# ATOM_-_3x_Attenuverter_Rev6.net
KiCad netlist of a schematic drawn in EAGLE
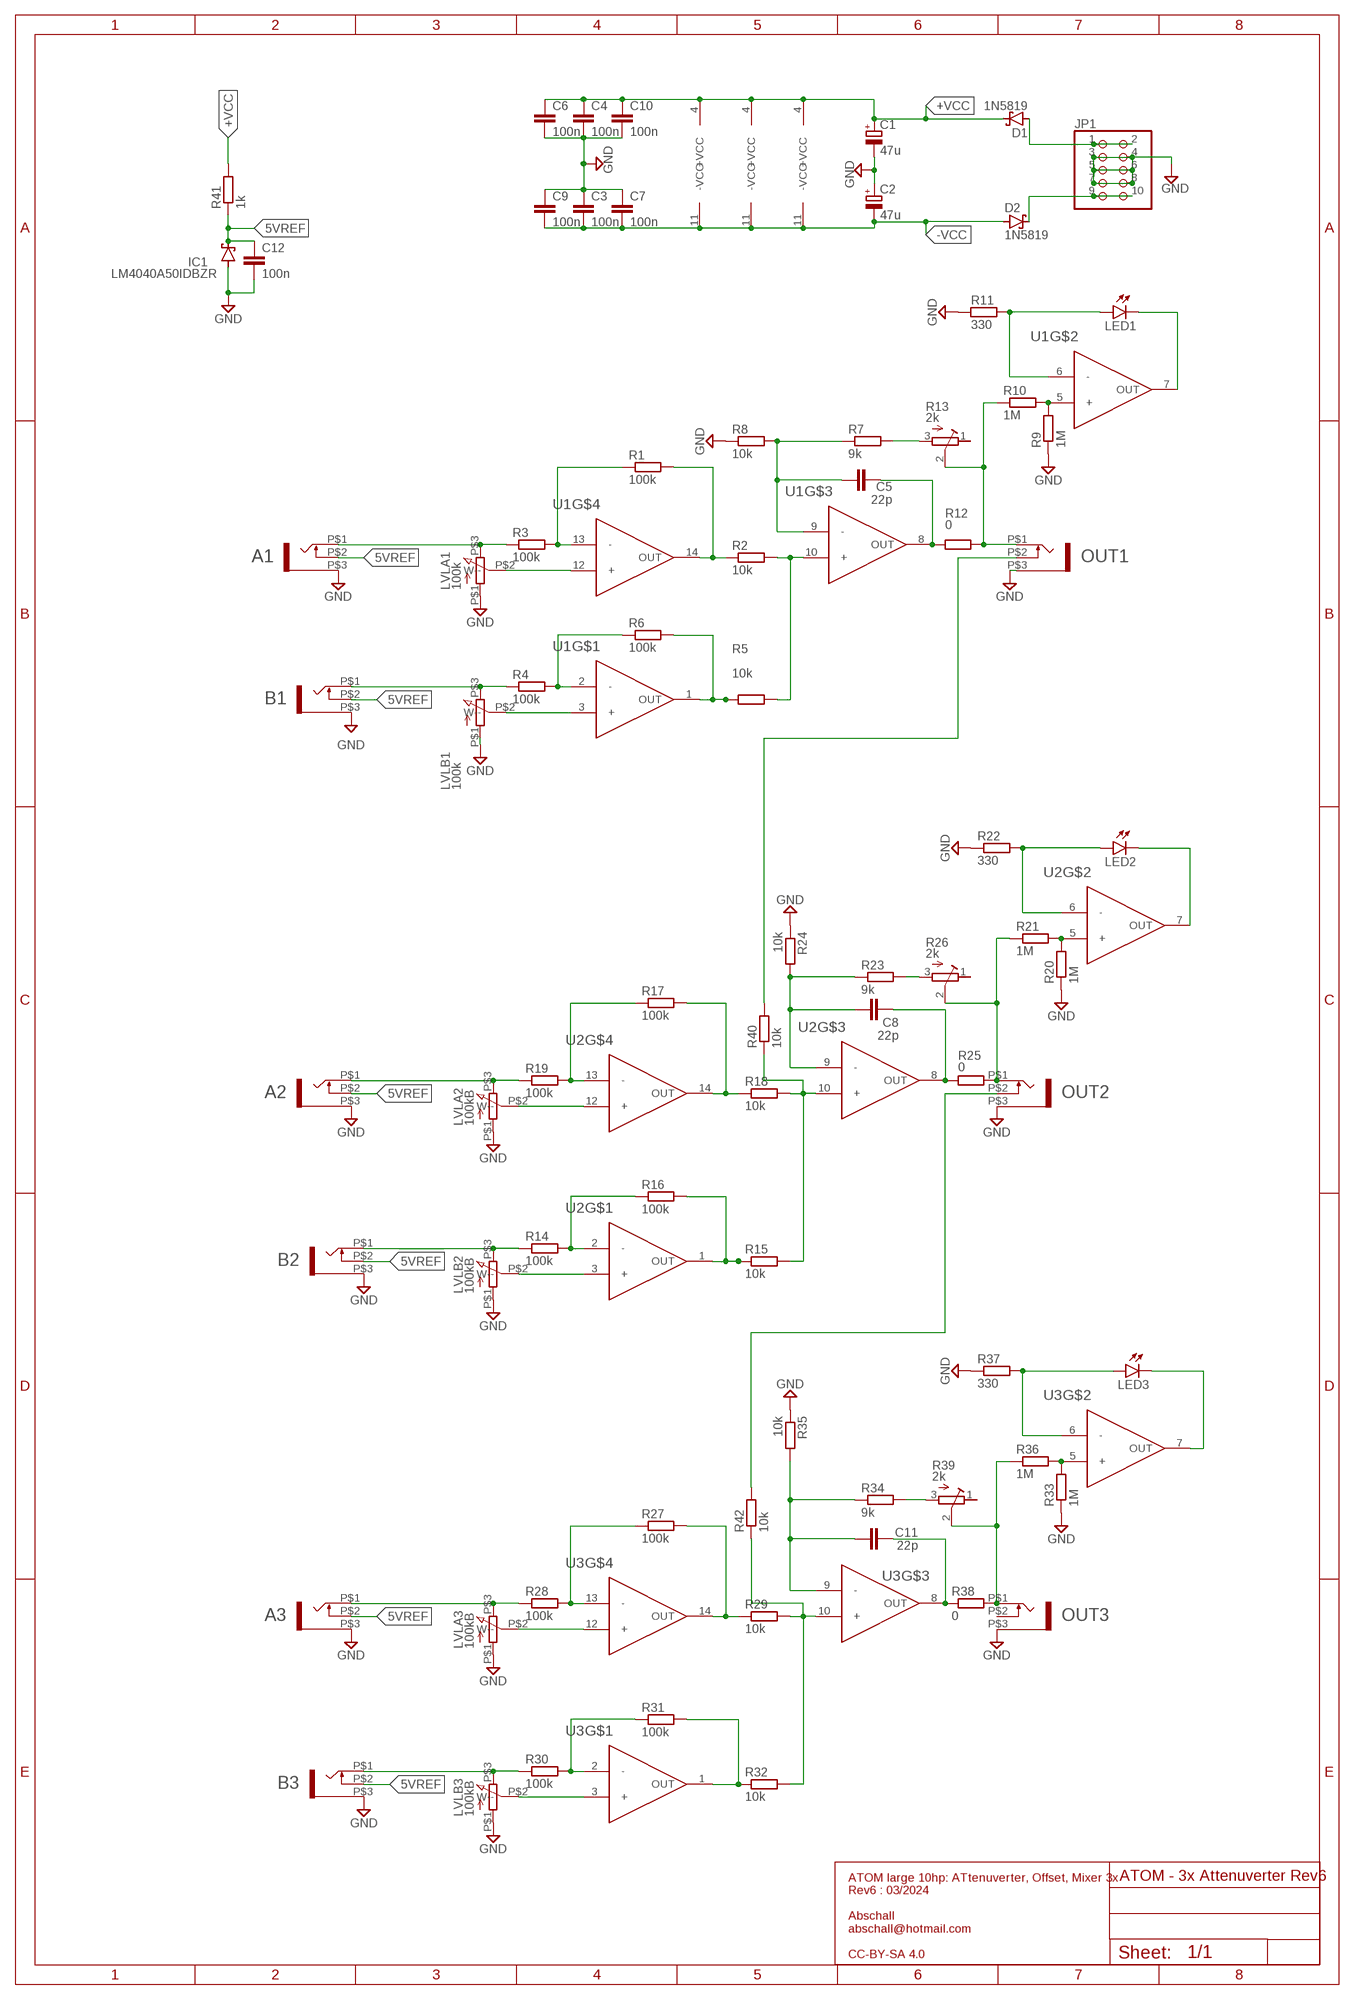
[diagram p0: schematic, sheet 1]

(export (version "E")
  (design (tool "Eeschema 10.0.6"))
  (components
    (comp (ref "A1")
      (value "WQP-PJ301M-12_JACK")
      (footprint "eagle-import:WQP-PJ301M-12_JACK")
      (libsource (lib "eagle-import") (part "WQP-PJ301M-12_JACK"))
    )
    (comp (ref "A2")
      (value "WQP-PJ301M-12_JACK")
      (footprint "eagle-import:WQP-PJ301M-12_JACK")
      (libsource (lib "eagle-import") (part "WQP-PJ301M-12_JACK"))
    )
    (comp (ref "A3")
      (value "WQP-PJ301M-12_JACK")
      (footprint "eagle-import:WQP-PJ301M-12_JACK")
      (libsource (lib "eagle-import") (part "WQP-PJ301M-12_JACK"))
    )
    (comp (ref "B1")
      (value "WQP-PJ301M-12_JACK")
      (footprint "eagle-import:WQP-PJ301M-12_JACK")
      (libsource (lib "eagle-import") (part "WQP-PJ301M-12_JACK"))
    )
    (comp (ref "B2")
      (value "WQP-PJ301M-12_JACK")
      (footprint "eagle-import:WQP-PJ301M-12_JACK")
      (libsource (lib "eagle-import") (part "WQP-PJ301M-12_JACK"))
    )
    (comp (ref "B3")
      (value "WQP-PJ301M-12_JACK")
      (footprint "eagle-import:WQP-PJ301M-12_JACK")
      (libsource (lib "eagle-import") (part "WQP-PJ301M-12_JACK"))
    )
    (comp (ref "C1")
      (value "47u")
      (footprint "eagle-import:PANASONIC_B")
      (libsource (lib "eagle-import") (part "CPOL-EUB"))
    )
    (comp (ref "C2")
      (value "47u")
      (footprint "eagle-import:PANASONIC_B")
      (libsource (lib "eagle-import") (part "CPOL-EUB"))
    )
    (comp (ref "C3")
      (value "100n")
      (footprint "eagle-import:C0805")
      (libsource (lib "eagle-import") (part "C-EUC0805"))
    )
    (comp (ref "C4")
      (value "100n")
      (footprint "eagle-import:C0805")
      (libsource (lib "eagle-import") (part "C-EUC0805"))
    )
    (comp (ref "C5")
      (value "22p")
      (footprint "eagle-import:C0805")
      (libsource (lib "eagle-import") (part "C-EUC0805"))
    )
    (comp (ref "C6")
      (value "100n")
      (footprint "eagle-import:C0805")
      (libsource (lib "eagle-import") (part "C-EUC0805"))
    )
    (comp (ref "C7")
      (value "100n")
      (footprint "eagle-import:C0805")
      (libsource (lib "eagle-import") (part "C-EUC0805"))
    )
    (comp (ref "C8")
      (value "22p")
      (footprint "eagle-import:C0805")
      (libsource (lib "eagle-import") (part "C-EUC0805"))
    )
    (comp (ref "C9")
      (value "100n")
      (footprint "eagle-import:C0805")
      (libsource (lib "eagle-import") (part "C-EUC0805"))
    )
    (comp (ref "C10")
      (value "100n")
      (footprint "eagle-import:C0805")
      (libsource (lib "eagle-import") (part "C-EUC0805"))
    )
    (comp (ref "C11")
      (value "22p")
      (footprint "eagle-import:C0805")
      (libsource (lib "eagle-import") (part "C-EUC0805"))
    )
    (comp (ref "C12")
      (value "100n")
      (footprint "eagle-import:C0805")
      (libsource (lib "eagle-import") (part "C-EUC0805"))
    )
    (comp (ref "D1")
      (value "1N5819")
      (footprint "eagle-import:SOD123")
      (libsource (lib "eagle-import") (part "1N5819"))
    )
    (comp (ref "D2")
      (value "1N5819")
      (footprint "eagle-import:SOD123")
      (libsource (lib "eagle-import") (part "1N5819"))
    )
    (comp (ref "IC1")
      (value "LM4040A50IDBZR")
      (footprint "eagle-import:SOT23")
      (libsource (lib "eagle-import") (part "LM4040"))
    )
    (comp (ref "JP1")
      (value "PINHD-2X5")
      (footprint "eagle-import:2X05")
      (libsource (lib "eagle-import") (part "PINHD-2X5"))
    )
    (comp (ref "LED1")
      (value "LED3MM")
      (footprint "eagle-import:LED3MM")
      (libsource (lib "eagle-import") (part "LED3MM"))
    )
    (comp (ref "LED2")
      (value "LED3MM")
      (footprint "eagle-import:LED3MM")
      (libsource (lib "eagle-import") (part "LED3MM"))
    )
    (comp (ref "LED3")
      (value "LED3MM")
      (footprint "eagle-import:LED3MM")
      (libsource (lib "eagle-import") (part "LED3MM"))
    )
    (comp (ref "LVLA1")
      (value "100k")
      (footprint "eagle-import:ALPHA9MM")
      (libsource (lib "eagle-import") (part "ALPHA9MM"))
    )
    (comp (ref "LVLA2")
      (value "100kB")
      (footprint "eagle-import:ALPHA9MM")
      (libsource (lib "eagle-import") (part "ALPHA9MM"))
    )
    (comp (ref "LVLA3")
      (value "100kB")
      (footprint "eagle-import:ALPHA9MM")
      (libsource (lib "eagle-import") (part "ALPHA9MM"))
    )
    (comp (ref "LVLB1")
      (value "100k")
      (footprint "eagle-import:ALPHA9MM")
      (libsource (lib "eagle-import") (part "ALPHA9MM"))
    )
    (comp (ref "LVLB2")
      (value "100kB")
      (footprint "eagle-import:ALPHA9MM")
      (libsource (lib "eagle-import") (part "ALPHA9MM"))
    )
    (comp (ref "LVLB3")
      (value "100kB")
      (footprint "eagle-import:ALPHA9MM")
      (libsource (lib "eagle-import") (part "ALPHA9MM"))
    )
    (comp (ref "OUT1")
      (value "WQP-PJ301M-12_JACK")
      (footprint "eagle-import:WQP-PJ301M-12_JACK")
      (libsource (lib "eagle-import") (part "WQP-PJ301M-12_JACK"))
    )
    (comp (ref "OUT2")
      (value "WQP-PJ301M-12_JACK")
      (footprint "eagle-import:WQP-PJ301M-12_JACK")
      (libsource (lib "eagle-import") (part "WQP-PJ301M-12_JACK"))
    )
    (comp (ref "OUT3")
      (value "WQP-PJ301M-12_JACK")
      (footprint "eagle-import:WQP-PJ301M-12_JACK")
      (libsource (lib "eagle-import") (part "WQP-PJ301M-12_JACK"))
    )
    (comp (ref "R1")
      (value "100k")
      (footprint "eagle-import:R0805")
      (libsource (lib "eagle-import") (part "R-EU_R0805"))
    )
    (comp (ref "R2")
      (value "10k")
      (footprint "eagle-import:R0805")
      (libsource (lib "eagle-import") (part "R-EU_R0805"))
    )
    (comp (ref "R3")
      (value "100k")
      (footprint "eagle-import:R0805")
      (libsource (lib "eagle-import") (part "R-EU_R0805"))
    )
    (comp (ref "R4")
      (value "100k")
      (footprint "eagle-import:R0805")
      (libsource (lib "eagle-import") (part "R-EU_R0805"))
    )
    (comp (ref "R5")
      (value "10k")
      (footprint "eagle-import:R0805")
      (libsource (lib "eagle-import") (part "R-EU_R0805"))
    )
    (comp (ref "R6")
      (value "100k")
      (footprint "eagle-import:R0805")
      (libsource (lib "eagle-import") (part "R-EU_R0805"))
    )
    (comp (ref "R7")
      (value "9k")
      (footprint "eagle-import:R0805")
      (libsource (lib "eagle-import") (part "R-EU_R0805"))
    )
    (comp (ref "R8")
      (value "10k")
      (footprint "eagle-import:R0805")
      (libsource (lib "eagle-import") (part "R-EU_R0805"))
    )
    (comp (ref "R9")
      (value "1M")
      (footprint "eagle-import:R0805")
      (libsource (lib "eagle-import") (part "R-EU_R0805"))
    )
    (comp (ref "R10")
      (value "1M")
      (footprint "eagle-import:R0805")
      (libsource (lib "eagle-import") (part "R-EU_R0805"))
    )
    (comp (ref "R11")
      (value "330")
      (footprint "eagle-import:R0805")
      (libsource (lib "eagle-import") (part "R-EU_R0805"))
    )
    (comp (ref "R12")
      (value "0")
      (footprint "eagle-import:R0805")
      (libsource (lib "eagle-import") (part "R-EU_R0805"))
    )
    (comp (ref "R13")
      (value "2k")
      (footprint "eagle-import:RTRIM3314J")
      (libsource (lib "eagle-import") (part "R-TRIMM3314J"))
    )
    (comp (ref "R14")
      (value "100k")
      (footprint "eagle-import:R0805")
      (libsource (lib "eagle-import") (part "R-EU_R0805"))
    )
    (comp (ref "R15")
      (value "10k")
      (footprint "eagle-import:R0805")
      (libsource (lib "eagle-import") (part "R-EU_R0805"))
    )
    (comp (ref "R16")
      (value "100k")
      (footprint "eagle-import:R0805")
      (libsource (lib "eagle-import") (part "R-EU_R0805"))
    )
    (comp (ref "R17")
      (value "100k")
      (footprint "eagle-import:R0805")
      (libsource (lib "eagle-import") (part "R-EU_R0805"))
    )
    (comp (ref "R18")
      (value "10k")
      (footprint "eagle-import:R0805")
      (libsource (lib "eagle-import") (part "R-EU_R0805"))
    )
    (comp (ref "R19")
      (value "100k")
      (footprint "eagle-import:R0805")
      (libsource (lib "eagle-import") (part "R-EU_R0805"))
    )
    (comp (ref "R20")
      (value "1M")
      (footprint "eagle-import:R0805")
      (libsource (lib "eagle-import") (part "R-EU_R0805"))
    )
    (comp (ref "R21")
      (value "1M")
      (footprint "eagle-import:R0805")
      (libsource (lib "eagle-import") (part "R-EU_R0805"))
    )
    (comp (ref "R22")
      (value "330")
      (footprint "eagle-import:R0805")
      (libsource (lib "eagle-import") (part "R-EU_R0805"))
    )
    (comp (ref "R23")
      (value "9k")
      (footprint "eagle-import:R0805")
      (libsource (lib "eagle-import") (part "R-EU_R0805"))
    )
    (comp (ref "R24")
      (value "10k")
      (footprint "eagle-import:R0805")
      (libsource (lib "eagle-import") (part "R-EU_R0805"))
    )
    (comp (ref "R25")
      (value "0")
      (footprint "eagle-import:R0805")
      (libsource (lib "eagle-import") (part "R-EU_R0805"))
    )
    (comp (ref "R26")
      (value "2k")
      (footprint "eagle-import:RTRIM3314J")
      (libsource (lib "eagle-import") (part "R-TRIMM3314J"))
    )
    (comp (ref "R27")
      (value "100k")
      (footprint "eagle-import:R0805")
      (libsource (lib "eagle-import") (part "R-EU_R0805"))
    )
    (comp (ref "R28")
      (value "100k")
      (footprint "eagle-import:R0805")
      (libsource (lib "eagle-import") (part "R-EU_R0805"))
    )
    (comp (ref "R29")
      (value "10k")
      (footprint "eagle-import:R0805")
      (libsource (lib "eagle-import") (part "R-EU_R0805"))
    )
    (comp (ref "R30")
      (value "100k")
      (footprint "eagle-import:R0805")
      (libsource (lib "eagle-import") (part "R-EU_R0805"))
    )
    (comp (ref "R31")
      (value "100k")
      (footprint "eagle-import:R0805")
      (libsource (lib "eagle-import") (part "R-EU_R0805"))
    )
    (comp (ref "R32")
      (value "10k")
      (footprint "eagle-import:R0805")
      (libsource (lib "eagle-import") (part "R-EU_R0805"))
    )
    (comp (ref "R33")
      (value "1M")
      (footprint "eagle-import:R0805")
      (libsource (lib "eagle-import") (part "R-EU_R0805"))
    )
    (comp (ref "R34")
      (value "9k")
      (footprint "eagle-import:R0805")
      (libsource (lib "eagle-import") (part "R-EU_R0805"))
    )
    (comp (ref "R35")
      (value "10k")
      (footprint "eagle-import:R0805")
      (libsource (lib "eagle-import") (part "R-EU_R0805"))
    )
    (comp (ref "R36")
      (value "1M")
      (footprint "eagle-import:R0805")
      (libsource (lib "eagle-import") (part "R-EU_R0805"))
    )
    (comp (ref "R37")
      (value "330")
      (footprint "eagle-import:R0805")
      (libsource (lib "eagle-import") (part "R-EU_R0805"))
    )
    (comp (ref "R38")
      (value "0")
      (footprint "eagle-import:R0805")
      (libsource (lib "eagle-import") (part "R-EU_R0805"))
    )
    (comp (ref "R39")
      (value "2k")
      (footprint "eagle-import:RTRIM3314J")
      (libsource (lib "eagle-import") (part "R-TRIMM3314J"))
    )
    (comp (ref "R40")
      (value "10k")
      (footprint "eagle-import:R0805")
      (libsource (lib "eagle-import") (part "R-EU_R0805"))
    )
    (comp (ref "R41")
      (value "1k")
      (footprint "eagle-import:R0805")
      (libsource (lib "eagle-import") (part "R-EU_R0805"))
    )
    (comp (ref "R42")
      (value "10k")
      (footprint "eagle-import:R0805")
      (libsource (lib "eagle-import") (part "R-EU_R0805"))
    )
    (comp (ref "U1")
      (value "TL74H")
      (footprint "eagle-import:SO14")
      (libsource (lib "eagle-import") (part "TL74H"))
    )
    (comp (ref "U2")
      (value "TL74H")
      (footprint "eagle-import:SO14")
      (libsource (lib "eagle-import") (part "TL74H"))
    )
    (comp (ref "U3")
      (value "TL74H")
      (footprint "eagle-import:SO14")
      (libsource (lib "eagle-import") (part "TL74H"))
    )
  )
  (nets
    (net (code "1") (name "+VCC") (class "Default")
      (node (ref "C1") (pin "+") (pinfunction "+_+") (pintype "passive"))
      (node (ref "C10") (pin "1") (pinfunction "1_1") (pintype "passive"))
      (node (ref "C4") (pin "1") (pinfunction "1_1") (pintype "passive"))
      (node (ref "C6") (pin "1") (pinfunction "1_1") (pintype "passive"))
      (node (ref "D1") (pin "C") (pinfunction "C_C") (pintype "passive"))
      (node (ref "R41") (pin "2") (pinfunction "2_2") (pintype "passive"))
      (node (ref "U1") (pin "4") (pinfunction "+VCC_4") (pintype "power_in"))
      (node (ref "U2") (pin "4") (pinfunction "+VCC_4") (pintype "power_in"))
      (node (ref "U3") (pin "4") (pinfunction "+VCC_4") (pintype "power_in"))
    )
    (net (code "2") (name "-VCC") (class "Default")
      (node (ref "C2") (pin "-") (pinfunction "-_-") (pintype "passive"))
      (node (ref "C3") (pin "2") (pinfunction "2_2") (pintype "passive"))
      (node (ref "C7") (pin "2") (pinfunction "2_2") (pintype "passive"))
      (node (ref "C9") (pin "2") (pinfunction "2_2") (pintype "passive"))
      (node (ref "D2") (pin "A") (pinfunction "A_A") (pintype "passive"))
      (node (ref "U1") (pin "11") (pinfunction "-VCC_11") (pintype "power_in"))
      (node (ref "U2") (pin "11") (pinfunction "-VCC_11") (pintype "power_in"))
      (node (ref "U3") (pin "11") (pinfunction "-VCC_11") (pintype "power_in"))
    )
    (net (code "3") (name "5VREF") (class "Default")
      (node (ref "A1") (pin "P$2") (pinfunction "3_P$2") (pintype "passive"))
      (node (ref "A2") (pin "P$2") (pinfunction "3_P$2") (pintype "passive"))
      (node (ref "A3") (pin "P$2") (pinfunction "3_P$2") (pintype "passive"))
      (node (ref "B1") (pin "P$2") (pinfunction "3_P$2") (pintype "passive"))
      (node (ref "B2") (pin "P$2") (pinfunction "3_P$2") (pintype "passive"))
      (node (ref "B3") (pin "P$2") (pinfunction "3_P$2") (pintype "passive"))
      (node (ref "C12") (pin "1") (pinfunction "1_1") (pintype "passive"))
      (node (ref "IC1") (pin "1") (pinfunction "C_1") (pintype "passive"))
      (node (ref "R41") (pin "1") (pinfunction "1_1") (pintype "passive"))
    )
    (net (code "4") (name "GND") (class "Default")
      (node (ref "A1") (pin "P$3") (pinfunction "1_P$3") (pintype "passive"))
      (node (ref "A2") (pin "P$3") (pinfunction "1_P$3") (pintype "passive"))
      (node (ref "A3") (pin "P$3") (pinfunction "1_P$3") (pintype "passive"))
      (node (ref "B1") (pin "P$3") (pinfunction "1_P$3") (pintype "passive"))
      (node (ref "B2") (pin "P$3") (pinfunction "1_P$3") (pintype "passive"))
      (node (ref "B3") (pin "P$3") (pinfunction "1_P$3") (pintype "passive"))
      (node (ref "C1") (pin "-") (pinfunction "-_-") (pintype "passive"))
      (node (ref "C10") (pin "2") (pinfunction "2_2") (pintype "passive"))
      (node (ref "C12") (pin "2") (pinfunction "2_2") (pintype "passive"))
      (node (ref "C2") (pin "+") (pinfunction "+_+") (pintype "passive"))
      (node (ref "C3") (pin "1") (pinfunction "1_1") (pintype "passive"))
      (node (ref "C4") (pin "2") (pinfunction "2_2") (pintype "passive"))
      (node (ref "C6") (pin "2") (pinfunction "2_2") (pintype "passive"))
      (node (ref "C7") (pin "1") (pinfunction "1_1") (pintype "passive"))
      (node (ref "C9") (pin "1") (pinfunction "1_1") (pintype "passive"))
      (node (ref "IC1") (pin "2") (pinfunction "A_2") (pintype "passive"))
      (node (ref "JP1") (pin "3") (pinfunction "3_3") (pintype "passive"))
      (node (ref "JP1") (pin "4") (pinfunction "4_4") (pintype "passive"))
      (node (ref "JP1") (pin "5") (pinfunction "5_5") (pintype "passive"))
      (node (ref "JP1") (pin "6") (pinfunction "6_6") (pintype "passive"))
      (node (ref "JP1") (pin "7") (pinfunction "7_7") (pintype "passive"))
      (node (ref "JP1") (pin "8") (pinfunction "8_8") (pintype "passive"))
      (node (ref "LVLA1") (pin "P$1") (pinfunction "1_P$1") (pintype "passive"))
      (node (ref "LVLA2") (pin "P$1") (pinfunction "1_P$1") (pintype "passive"))
      (node (ref "LVLA3") (pin "P$1") (pinfunction "1_P$1") (pintype "passive"))
      (node (ref "LVLB1") (pin "P$1") (pinfunction "1_P$1") (pintype "passive"))
      (node (ref "LVLB2") (pin "P$1") (pinfunction "1_P$1") (pintype "passive"))
      (node (ref "LVLB3") (pin "P$1") (pinfunction "1_P$1") (pintype "passive"))
      (node (ref "OUT1") (pin "P$3") (pinfunction "1_P$3") (pintype "passive"))
      (node (ref "OUT2") (pin "P$3") (pinfunction "1_P$3") (pintype "passive"))
      (node (ref "OUT3") (pin "P$3") (pinfunction "1_P$3") (pintype "passive"))
      (node (ref "R11") (pin "1") (pinfunction "1_1") (pintype "passive"))
      (node (ref "R20") (pin "1") (pinfunction "1_1") (pintype "passive"))
      (node (ref "R22") (pin "1") (pinfunction "1_1") (pintype "passive"))
      (node (ref "R24") (pin "1") (pinfunction "1_1") (pintype "passive"))
      (node (ref "R33") (pin "1") (pinfunction "1_1") (pintype "passive"))
      (node (ref "R35") (pin "1") (pinfunction "1_1") (pintype "passive"))
      (node (ref "R37") (pin "1") (pinfunction "1_1") (pintype "passive"))
      (node (ref "R8") (pin "1") (pinfunction "1_1") (pintype "passive"))
      (node (ref "R9") (pin "1") (pinfunction "1_1") (pintype "passive"))
    )
    (net (code "5") (name "Net-(A1-2)") (class "Default")
      (node (ref "A1") (pin "P$1") (pinfunction "2_P$1") (pintype "passive"))
      (node (ref "LVLA1") (pin "P$3") (pinfunction "3_P$3") (pintype "passive"))
      (node (ref "R3") (pin "1") (pinfunction "1_1") (pintype "passive"))
    )
    (net (code "6") (name "Net-(A2-2)") (class "Default")
      (node (ref "A2") (pin "P$1") (pinfunction "2_P$1") (pintype "passive"))
      (node (ref "LVLA2") (pin "P$3") (pinfunction "3_P$3") (pintype "passive"))
      (node (ref "R19") (pin "1") (pinfunction "1_1") (pintype "passive"))
    )
    (net (code "7") (name "Net-(A3-2)") (class "Default")
      (node (ref "A3") (pin "P$1") (pinfunction "2_P$1") (pintype "passive"))
      (node (ref "LVLA3") (pin "P$3") (pinfunction "3_P$3") (pintype "passive"))
      (node (ref "R28") (pin "1") (pinfunction "1_1") (pintype "passive"))
    )
    (net (code "8") (name "Net-(B1-2)") (class "Default")
      (node (ref "B1") (pin "P$1") (pinfunction "2_P$1") (pintype "passive"))
      (node (ref "LVLB1") (pin "P$3") (pinfunction "3_P$3") (pintype "passive"))
      (node (ref "R4") (pin "1") (pinfunction "1_1") (pintype "passive"))
    )
    (net (code "9") (name "Net-(B2-2)") (class "Default")
      (node (ref "B2") (pin "P$1") (pinfunction "2_P$1") (pintype "passive"))
      (node (ref "LVLB2") (pin "P$3") (pinfunction "3_P$3") (pintype "passive"))
      (node (ref "R14") (pin "1") (pinfunction "1_1") (pintype "passive"))
    )
    (net (code "10") (name "Net-(B3-2)") (class "Default")
      (node (ref "B3") (pin "P$1") (pinfunction "2_P$1") (pintype "passive"))
      (node (ref "LVLB3") (pin "P$3") (pinfunction "3_P$3") (pintype "passive"))
      (node (ref "R30") (pin "1") (pinfunction "1_1") (pintype "passive"))
    )
    (net (code "11") (name "Net-(D1-PadA)") (class "Default")
      (node (ref "D1") (pin "A") (pinfunction "A_A") (pintype "passive"))
      (node (ref "JP1") (pin "1") (pinfunction "1_1") (pintype "passive"))
      (node (ref "JP1") (pin "2") (pinfunction "2_2") (pintype "passive"))
    )
    (net (code "12") (name "Net-(D2-PadC)") (class "Default")
      (node (ref "D2") (pin "C") (pinfunction "C_C") (pintype "passive"))
      (node (ref "JP1") (pin "10") (pinfunction "10_10") (pintype "passive"))
      (node (ref "JP1") (pin "9") (pinfunction "9_9") (pintype "passive"))
    )
    (net (code "13") (name "Net-(LED1-C)") (class "Default")
      (node (ref "LED1") (pin "K") (pinfunction "C_K") (pintype "passive"))
      (node (ref "U1") (pin "7") (pinfunction "OUT_7") (pintype "output"))
    )
    (net (code "14") (name "Net-(LED2-C)") (class "Default")
      (node (ref "LED2") (pin "K") (pinfunction "C_K") (pintype "passive"))
      (node (ref "U2") (pin "7") (pinfunction "OUT_7") (pintype "output"))
    )
    (net (code "15") (name "Net-(LED3-C)") (class "Default")
      (node (ref "LED3") (pin "K") (pinfunction "C_K") (pintype "passive"))
      (node (ref "U3") (pin "7") (pinfunction "OUT_7") (pintype "output"))
    )
    (net (code "16") (name "Net-(LVLA1-W--)") (class "Default")
      (node (ref "LVLA1") (pin "P$2") (pinfunction "W--_P$2") (pintype "passive"))
      (node (ref "U1") (pin "12") (pinfunction "+_12") (pintype "input"))
    )
    (net (code "17") (name "Net-(LVLA2-W--)") (class "Default")
      (node (ref "LVLA2") (pin "P$2") (pinfunction "W--_P$2") (pintype "passive"))
      (node (ref "U2") (pin "12") (pinfunction "+_12") (pintype "input"))
    )
    (net (code "18") (name "Net-(LVLA3-W--)") (class "Default")
      (node (ref "LVLA3") (pin "P$2") (pinfunction "W--_P$2") (pintype "passive"))
      (node (ref "U3") (pin "12") (pinfunction "+_12") (pintype "input"))
    )
    (net (code "19") (name "Net-(LVLB1-W--)") (class "Default")
      (node (ref "LVLB1") (pin "P$2") (pinfunction "W--_P$2") (pintype "passive"))
      (node (ref "U1") (pin "3") (pinfunction "+_3") (pintype "input"))
    )
    (net (code "20") (name "Net-(LVLB2-W--)") (class "Default")
      (node (ref "LVLB2") (pin "P$2") (pinfunction "W--_P$2") (pintype "passive"))
      (node (ref "U2") (pin "3") (pinfunction "+_3") (pintype "input"))
    )
    (net (code "21") (name "Net-(LVLB3-W--)") (class "Default")
      (node (ref "LVLB3") (pin "P$2") (pinfunction "W--_P$2") (pintype "passive"))
      (node (ref "U3") (pin "3") (pinfunction "+_3") (pintype "input"))
    )
    (net (code "22") (name "Net-(OUT1-2)") (class "Default")
      (node (ref "OUT1") (pin "P$1") (pinfunction "2_P$1") (pintype "passive"))
      (node (ref "R10") (pin "1") (pinfunction "1_1") (pintype "passive"))
      (node (ref "R12") (pin "2") (pinfunction "2_2") (pintype "passive"))
      (node (ref "R13") (pin "2") (pinfunction "S_2") (pintype "passive"))
    )
    (net (code "23") (name "Net-(OUT1-3)") (class "Default")
      (node (ref "OUT1") (pin "P$2") (pinfunction "3_P$2") (pintype "passive"))
      (node (ref "R40") (pin "2") (pinfunction "2_2") (pintype "passive"))
    )
    (net (code "24") (name "Net-(OUT2-2)") (class "Default")
      (node (ref "OUT2") (pin "P$1") (pinfunction "2_P$1") (pintype "passive"))
      (node (ref "R21") (pin "1") (pinfunction "1_1") (pintype "passive"))
      (node (ref "R25") (pin "2") (pinfunction "2_2") (pintype "passive"))
      (node (ref "R26") (pin "2") (pinfunction "S_2") (pintype "passive"))
    )
    (net (code "25") (name "Net-(OUT2-3)") (class "Default")
      (node (ref "OUT2") (pin "P$2") (pinfunction "3_P$2") (pintype "passive"))
      (node (ref "R42") (pin "2") (pinfunction "2_2") (pintype "passive"))
    )
    (net (code "26") (name "Net-(OUT3-2)") (class "Default")
      (node (ref "OUT3") (pin "P$1") (pinfunction "2_P$1") (pintype "passive"))
      (node (ref "R36") (pin "1") (pinfunction "1_1") (pintype "passive"))
      (node (ref "R38") (pin "2") (pinfunction "2_2") (pintype "passive"))
      (node (ref "R39") (pin "2") (pinfunction "S_2") (pintype "passive"))
    )
    (net (code "27") (name "Net-(R13-A)") (class "Default")
      (node (ref "R13") (pin "3") (pinfunction "A_3") (pintype "passive"))
      (node (ref "R7") (pin "2") (pinfunction "2_2") (pintype "passive"))
    )
    (net (code "28") (name "Net-(R26-A)") (class "Default")
      (node (ref "R23") (pin "2") (pinfunction "2_2") (pintype "passive"))
      (node (ref "R26") (pin "3") (pinfunction "A_3") (pintype "passive"))
    )
    (net (code "29") (name "Net-(R39-A)") (class "Default")
      (node (ref "R34") (pin "2") (pinfunction "2_2") (pintype "passive"))
      (node (ref "R39") (pin "3") (pinfunction "A_3") (pintype "passive"))
    )
    (net (code "30") (name "Net-(U1A--)") (class "Default")
      (node (ref "R4") (pin "2") (pinfunction "2_2") (pintype "passive"))
      (node (ref "R6") (pin "1") (pinfunction "1_1") (pintype "passive"))
      (node (ref "U1") (pin "2") (pinfunction "-_2") (pintype "input"))
    )
    (net (code "31") (name "Net-(U1A-OUT)") (class "Default")
      (node (ref "R5") (pin "1") (pinfunction "1_1") (pintype "passive"))
      (node (ref "R6") (pin "2") (pinfunction "2_2") (pintype "passive"))
      (node (ref "U1") (pin "1") (pinfunction "OUT_1") (pintype "output"))
    )
    (net (code "32") (name "Net-(U1B-+)") (class "Default")
      (node (ref "R10") (pin "2") (pinfunction "2_2") (pintype "passive"))
      (node (ref "R9") (pin "2") (pinfunction "2_2") (pintype "passive"))
      (node (ref "U1") (pin "5") (pinfunction "+_5") (pintype "input"))
    )
    (net (code "33") (name "Net-(U1B--)") (class "Default")
      (node (ref "LED1") (pin "A") (pinfunction "A_A") (pintype "passive"))
      (node (ref "R11") (pin "2") (pinfunction "2_2") (pintype "passive"))
      (node (ref "U1") (pin "6") (pinfunction "-_6") (pintype "input"))
    )
    (net (code "34") (name "Net-(U1C-+)") (class "Default")
      (node (ref "R2") (pin "2") (pinfunction "2_2") (pintype "passive"))
      (node (ref "R5") (pin "2") (pinfunction "2_2") (pintype "passive"))
      (node (ref "U1") (pin "10") (pinfunction "+_10") (pintype "input"))
    )
    (net (code "35") (name "Net-(U1C--)") (class "Default")
      (node (ref "C5") (pin "1") (pinfunction "1_1") (pintype "passive"))
      (node (ref "R7") (pin "1") (pinfunction "1_1") (pintype "passive"))
      (node (ref "R8") (pin "2") (pinfunction "2_2") (pintype "passive"))
      (node (ref "U1") (pin "9") (pinfunction "-_9") (pintype "input"))
    )
    (net (code "36") (name "Net-(U1C-OUT)") (class "Default")
      (node (ref "C5") (pin "2") (pinfunction "2_2") (pintype "passive"))
      (node (ref "R12") (pin "1") (pinfunction "1_1") (pintype "passive"))
      (node (ref "U1") (pin "8") (pinfunction "OUT_8") (pintype "output"))
    )
    (net (code "37") (name "Net-(U1D--)") (class "Default")
      (node (ref "R1") (pin "1") (pinfunction "1_1") (pintype "passive"))
      (node (ref "R3") (pin "2") (pinfunction "2_2") (pintype "passive"))
      (node (ref "U1") (pin "13") (pinfunction "-_13") (pintype "input"))
    )
    (net (code "38") (name "Net-(U1D-OUT)") (class "Default")
      (node (ref "R1") (pin "2") (pinfunction "2_2") (pintype "passive"))
      (node (ref "R2") (pin "1") (pinfunction "1_1") (pintype "passive"))
      (node (ref "U1") (pin "14") (pinfunction "OUT_14") (pintype "output"))
    )
    (net (code "39") (name "Net-(U2A--)") (class "Default")
      (node (ref "R14") (pin "2") (pinfunction "2_2") (pintype "passive"))
      (node (ref "R16") (pin "1") (pinfunction "1_1") (pintype "passive"))
      (node (ref "U2") (pin "2") (pinfunction "-_2") (pintype "input"))
    )
    (net (code "40") (name "Net-(U2A-OUT)") (class "Default")
      (node (ref "R15") (pin "1") (pinfunction "1_1") (pintype "passive"))
      (node (ref "R16") (pin "2") (pinfunction "2_2") (pintype "passive"))
      (node (ref "U2") (pin "1") (pinfunction "OUT_1") (pintype "output"))
    )
    (net (code "41") (name "Net-(U2B-+)") (class "Default")
      (node (ref "R20") (pin "2") (pinfunction "2_2") (pintype "passive"))
      (node (ref "R21") (pin "2") (pinfunction "2_2") (pintype "passive"))
      (node (ref "U2") (pin "5") (pinfunction "+_5") (pintype "input"))
    )
    (net (code "42") (name "Net-(U2B--)") (class "Default")
      (node (ref "LED2") (pin "A") (pinfunction "A_A") (pintype "passive"))
      (node (ref "R22") (pin "2") (pinfunction "2_2") (pintype "passive"))
      (node (ref "U2") (pin "6") (pinfunction "-_6") (pintype "input"))
    )
    (net (code "43") (name "Net-(U2C-+)") (class "Default")
      (node (ref "R15") (pin "2") (pinfunction "2_2") (pintype "passive"))
      (node (ref "R18") (pin "2") (pinfunction "2_2") (pintype "passive"))
      (node (ref "R40") (pin "1") (pinfunction "1_1") (pintype "passive"))
      (node (ref "U2") (pin "10") (pinfunction "+_10") (pintype "input"))
    )
    (net (code "44") (name "Net-(U2C--)") (class "Default")
      (node (ref "C8") (pin "1") (pinfunction "1_1") (pintype "passive"))
      (node (ref "R23") (pin "1") (pinfunction "1_1") (pintype "passive"))
      (node (ref "R24") (pin "2") (pinfunction "2_2") (pintype "passive"))
      (node (ref "U2") (pin "9") (pinfunction "-_9") (pintype "input"))
    )
    (net (code "45") (name "Net-(U2C-OUT)") (class "Default")
      (node (ref "C8") (pin "2") (pinfunction "2_2") (pintype "passive"))
      (node (ref "R25") (pin "1") (pinfunction "1_1") (pintype "passive"))
      (node (ref "U2") (pin "8") (pinfunction "OUT_8") (pintype "output"))
    )
    (net (code "46") (name "Net-(U2D--)") (class "Default")
      (node (ref "R17") (pin "1") (pinfunction "1_1") (pintype "passive"))
      (node (ref "R19") (pin "2") (pinfunction "2_2") (pintype "passive"))
      (node (ref "U2") (pin "13") (pinfunction "-_13") (pintype "input"))
    )
    (net (code "47") (name "Net-(U2D-OUT)") (class "Default")
      (node (ref "R17") (pin "2") (pinfunction "2_2") (pintype "passive"))
      (node (ref "R18") (pin "1") (pinfunction "1_1") (pintype "passive"))
      (node (ref "U2") (pin "14") (pinfunction "OUT_14") (pintype "output"))
    )
    (net (code "48") (name "Net-(U3A--)") (class "Default")
      (node (ref "R30") (pin "2") (pinfunction "2_2") (pintype "passive"))
      (node (ref "R31") (pin "1") (pinfunction "1_1") (pintype "passive"))
      (node (ref "U3") (pin "2") (pinfunction "-_2") (pintype "input"))
    )
    (net (code "49") (name "Net-(U3A-OUT)") (class "Default")
      (node (ref "R31") (pin "2") (pinfunction "2_2") (pintype "passive"))
      (node (ref "R32") (pin "1") (pinfunction "1_1") (pintype "passive"))
      (node (ref "U3") (pin "1") (pinfunction "OUT_1") (pintype "output"))
    )
    (net (code "50") (name "Net-(U3B-+)") (class "Default")
      (node (ref "R33") (pin "2") (pinfunction "2_2") (pintype "passive"))
      (node (ref "R36") (pin "2") (pinfunction "2_2") (pintype "passive"))
      (node (ref "U3") (pin "5") (pinfunction "+_5") (pintype "input"))
    )
    (net (code "51") (name "Net-(U3B--)") (class "Default")
      (node (ref "LED3") (pin "A") (pinfunction "A_A") (pintype "passive"))
      (node (ref "R37") (pin "2") (pinfunction "2_2") (pintype "passive"))
      (node (ref "U3") (pin "6") (pinfunction "-_6") (pintype "input"))
    )
    (net (code "52") (name "Net-(U3C-+)") (class "Default")
      (node (ref "R29") (pin "2") (pinfunction "2_2") (pintype "passive"))
      (node (ref "R32") (pin "2") (pinfunction "2_2") (pintype "passive"))
      (node (ref "R42") (pin "1") (pinfunction "1_1") (pintype "passive"))
      (node (ref "U3") (pin "10") (pinfunction "+_10") (pintype "input"))
    )
    (net (code "53") (name "Net-(U3C--)") (class "Default")
      (node (ref "C11") (pin "1") (pinfunction "1_1") (pintype "passive"))
      (node (ref "R34") (pin "1") (pinfunction "1_1") (pintype "passive"))
      (node (ref "R35") (pin "2") (pinfunction "2_2") (pintype "passive"))
      (node (ref "U3") (pin "9") (pinfunction "-_9") (pintype "input"))
    )
    (net (code "54") (name "Net-(U3C-OUT)") (class "Default")
      (node (ref "C11") (pin "2") (pinfunction "2_2") (pintype "passive"))
      (node (ref "R38") (pin "1") (pinfunction "1_1") (pintype "passive"))
      (node (ref "U3") (pin "8") (pinfunction "OUT_8") (pintype "output"))
    )
    (net (code "55") (name "Net-(U3D--)") (class "Default")
      (node (ref "R27") (pin "1") (pinfunction "1_1") (pintype "passive"))
      (node (ref "R28") (pin "2") (pinfunction "2_2") (pintype "passive"))
      (node (ref "U3") (pin "13") (pinfunction "-_13") (pintype "input"))
    )
    (net (code "56") (name "Net-(U3D-OUT)") (class "Default")
      (node (ref "R27") (pin "2") (pinfunction "2_2") (pintype "passive"))
      (node (ref "R29") (pin "1") (pinfunction "1_1") (pintype "passive"))
      (node (ref "U3") (pin "14") (pinfunction "OUT_14") (pintype "output"))
    )
    (net (code "57") (name "unconnected-(OUT3-3-PadP$2)") (class "Default")
      (node (ref "OUT3") (pin "P$2") (pinfunction "3_P$2") (pintype "passive"))
    )
    (net (code "58") (name "unconnected-(R13-E-Pad1)") (class "Default")
      (node (ref "R13") (pin "1") (pinfunction "E_1") (pintype "passive"))
    )
    (net (code "59") (name "unconnected-(R26-E-Pad1)") (class "Default")
      (node (ref "R26") (pin "1") (pinfunction "E_1") (pintype "passive"))
    )
    (net (code "60") (name "unconnected-(R39-E-Pad1)") (class "Default")
      (node (ref "R39") (pin "1") (pinfunction "E_1") (pintype "passive"))
    )
  )
)
